# CSR8635-V1.net
KiCad netlist of a schematic drawn in EAGLE
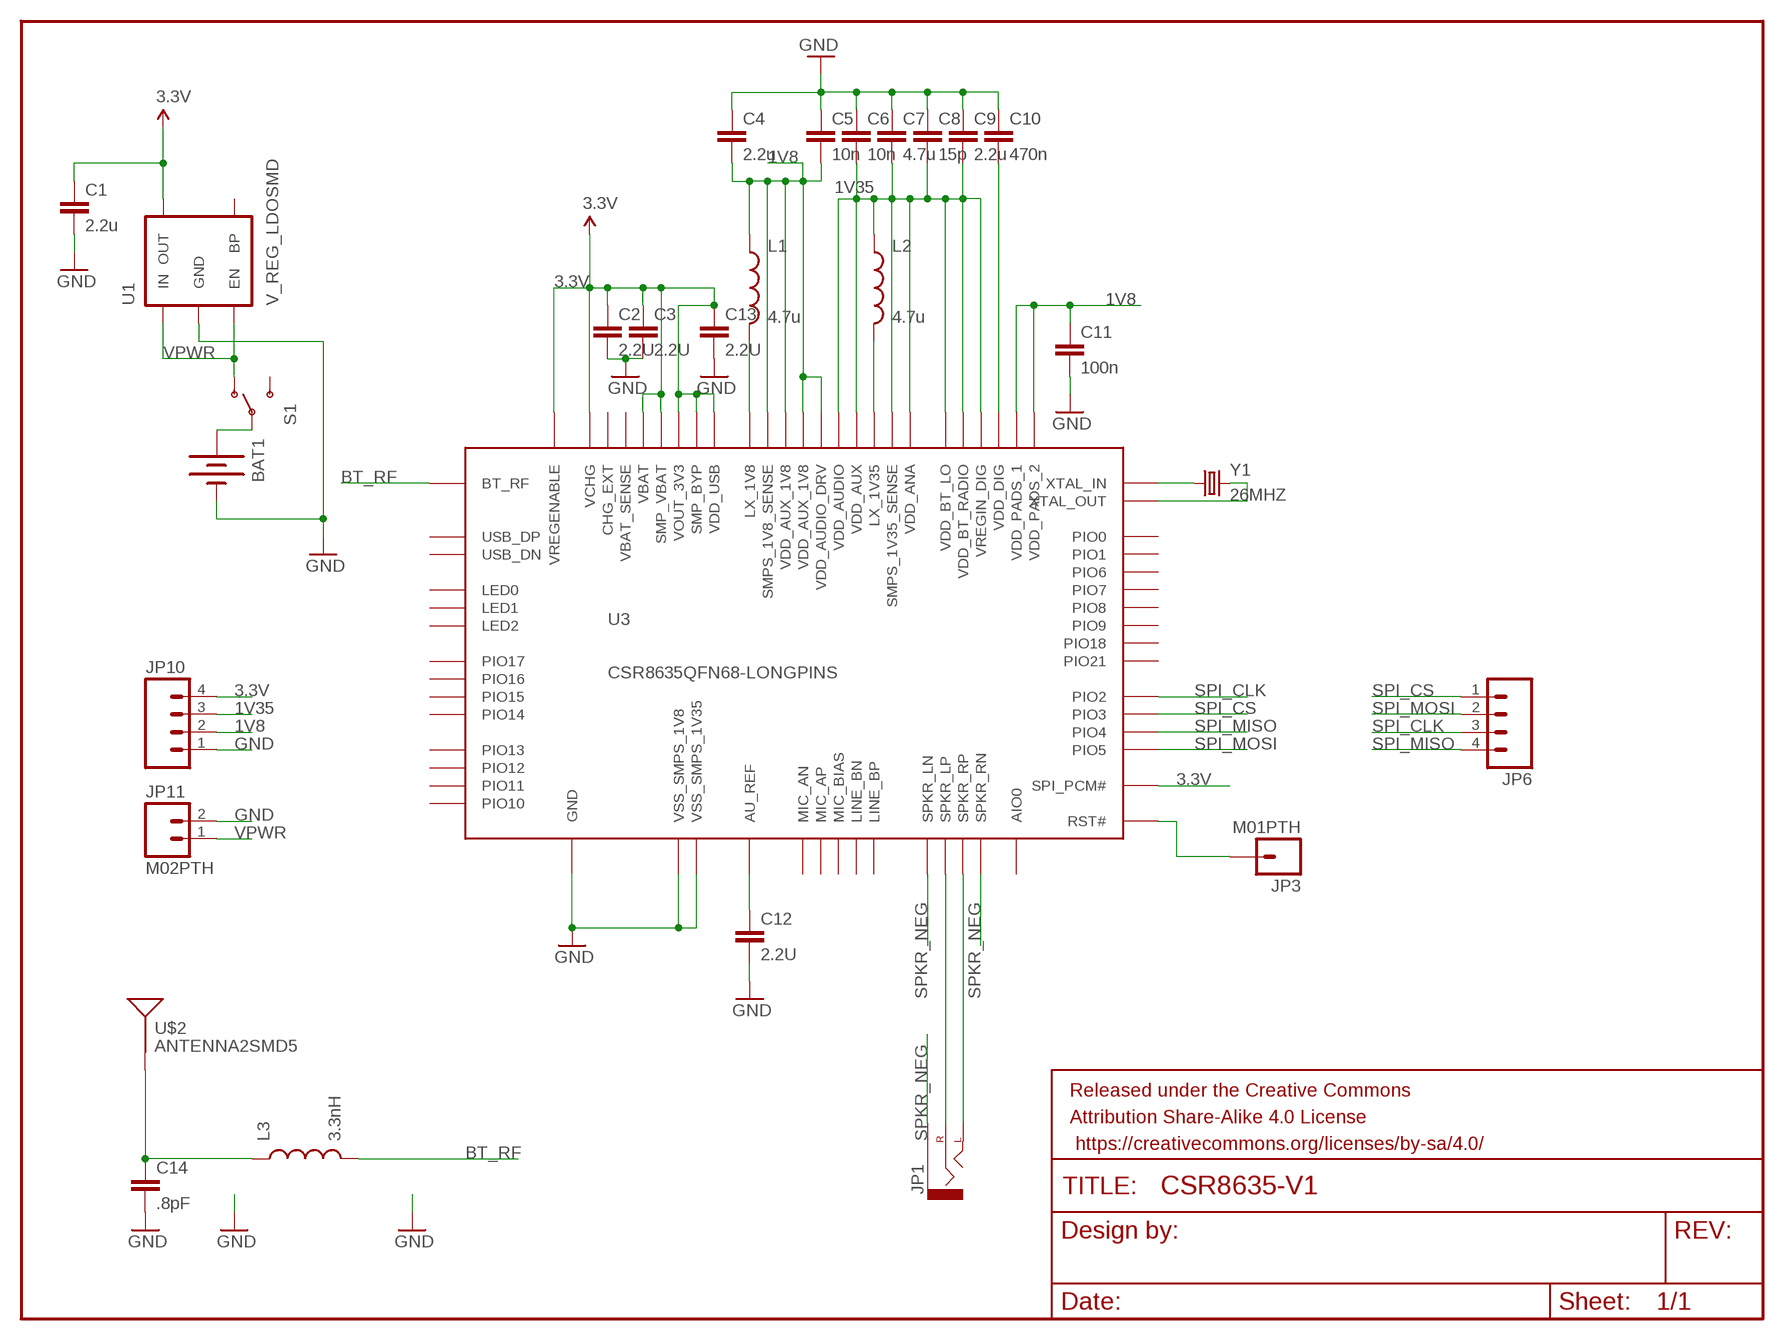
[diagram p0: schematic, sheet 1]

(export (version "E")
  (design (tool "Eeschema 10.0.6"))
  (components
    (comp (ref "BAT1")
      (value "BATTERY9V")
      (footprint "eagle-import:BATTCON_9V")
      (libsource (lib "eagle-import") (part "BATTERY9V"))
    )
    (comp (ref "C1")
      (value "2.2u")
      (footprint "eagle-import:0603-CAP")
      (libsource (lib "eagle-import") (part "CAP0603-CAP"))
    )
    (comp (ref "C2")
      (value "2.2U")
      (footprint "eagle-import:0603-CAP")
      (libsource (lib "eagle-import") (part "CAP0603-CAP"))
    )
    (comp (ref "C3")
      (value "2.2U")
      (footprint "eagle-import:0603-CAP")
      (libsource (lib "eagle-import") (part "CAP0603-CAP"))
    )
    (comp (ref "C4")
      (value "2.2u")
      (footprint "eagle-import:0603-CAP")
      (libsource (lib "eagle-import") (part "CAP0603-CAP"))
    )
    (comp (ref "C5")
      (value "10n")
      (footprint "eagle-import:0603-CAP")
      (libsource (lib "eagle-import") (part "CAP0603-CAP"))
    )
    (comp (ref "C6")
      (value "10n")
      (footprint "eagle-import:0603-CAP")
      (libsource (lib "eagle-import") (part "CAP0603-CAP"))
    )
    (comp (ref "C7")
      (value "4.7u")
      (footprint "eagle-import:0603-CAP")
      (libsource (lib "eagle-import") (part "CAP0603-CAP"))
    )
    (comp (ref "C8")
      (value "15p")
      (footprint "eagle-import:0603-CAP")
      (libsource (lib "eagle-import") (part "CAP0603-CAP"))
    )
    (comp (ref "C9")
      (value "2.2u")
      (footprint "eagle-import:0603-CAP")
      (libsource (lib "eagle-import") (part "CAP0603-CAP"))
    )
    (comp (ref "C10")
      (value "470n")
      (footprint "eagle-import:0603-CAP")
      (libsource (lib "eagle-import") (part "CAP0603-CAP"))
    )
    (comp (ref "C11")
      (value "100n")
      (footprint "eagle-import:0603-CAP")
      (libsource (lib "eagle-import") (part "CAP0603-CAP"))
    )
    (comp (ref "C12")
      (value "2.2U")
      (footprint "eagle-import:0603-CAP")
      (libsource (lib "eagle-import") (part "CAP0603-CAP"))
    )
    (comp (ref "C13")
      (value "2.2U")
      (footprint "eagle-import:0603-CAP")
      (libsource (lib "eagle-import") (part "CAP0603-CAP"))
    )
    (comp (ref "C14")
      (value ".8pF")
      (footprint "eagle-import:0603-CAP")
      (libsource (lib "eagle-import") (part "CAP0603-CAP"))
    )
    (comp (ref "FRAME1")
      (value "FRAME-LETTER")
      (footprint "eagle-import:CREATIVE_COMMONS")
      (libsource (lib "eagle-import") (part "FRAME-LETTER"))
    )
    (comp (ref "JP1")
      (value "AUDIO-JACKSMD2")
      (footprint "eagle-import:AUDIO-JACK-3.5MM-SMD")
      (libsource (lib "eagle-import") (part "AUDIO-JACKSMD2"))
    )
    (comp (ref "JP3")
      (value "M01PTH")
      (footprint "eagle-import:1X01")
      (libsource (lib "eagle-import") (part "M01PTH"))
    )
    (comp (ref "JP6")
      (value "M04PTH")
      (footprint "eagle-import:1X04")
      (libsource (lib "eagle-import") (part "M04PTH"))
    )
    (comp (ref "JP10")
      (value "M04PTH")
      (footprint "eagle-import:1X04")
      (libsource (lib "eagle-import") (part "M04PTH"))
    )
    (comp (ref "JP11")
      (value "M02PTH")
      (footprint "eagle-import:1X02")
      (libsource (lib "eagle-import") (part "M02PTH"))
    )
    (comp (ref "L1")
      (value "4.7u")
      (footprint "eagle-import:0805")
      (libsource (lib "eagle-import") (part "INDUCTOR0805"))
    )
    (comp (ref "L2")
      (value "4.7u")
      (footprint "eagle-import:0805")
      (libsource (lib "eagle-import") (part "INDUCTOR0805"))
    )
    (comp (ref "L3")
      (value "3.3nH")
      (footprint "eagle-import:0805")
      (libsource (lib "eagle-import") (part "INDUCTOR0805"))
    )
    (comp (ref "S1")
      (value "SWITCH-SPDTPTH")
      (footprint "eagle-import:SWITCH-SPDT")
      (libsource (lib "eagle-import") (part "SWITCH-SPDTPTH"))
    )
    (comp (ref "U$2")
      (value "ANTENNA2SMD5")
      (footprint "eagle-import:ANTENNA-CHIP5")
      (libsource (lib "eagle-import") (part "ANTENNA2SMD5"))
    )
    (comp (ref "U1")
      (value "V_REG_LDOSMD")
      (footprint "eagle-import:SOT23-5")
      (libsource (lib "eagle-import") (part "V_REG_LDOSMD"))
    )
    (comp (ref "U3")
      (value "CSR8635QFN68-LONGPINS")
      (footprint "eagle-import:QFN68")
      (libsource (lib "eagle-import") (part "CSR8635QFN68-LONGPINS"))
    )
    (comp (ref "Y1")
      (value "26MHZ")
      (footprint "eagle-import:HC49US")
      (libsource (lib "eagle-import") (part "CRYSTALHC49US"))
    )
  )
  (nets
    (net (code "1") (name "/1V8") (class "Default")
      (node (ref "C11") (pin "1") (pinfunction "1_1") (pintype "passive"))
      (node (ref "C4") (pin "2") (pinfunction "2_2") (pintype "passive"))
      (node (ref "C5") (pin "2") (pinfunction "2_2") (pintype "passive"))
      (node (ref "JP10") (pin "2") (pinfunction "2_2") (pintype "passive"))
      (node (ref "L1") (pin "1") (pinfunction "1_1") (pintype "passive"))
      (node (ref "U3") (pin "15") (pinfunction "VDD_AUX_1V8_15") (pintype "power_in"))
      (node (ref "U3") (pin "16") (pinfunction "VDD_AUX_1V8_16") (pintype "power_in"))
      (node (ref "U3") (pin "33") (pinfunction "VDD_PADS_1_33") (pintype "bidirectional"))
      (node (ref "U3") (pin "53") (pinfunction "SMPS_1V8_SENSE_53") (pintype "bidirectional"))
      (node (ref "U3") (pin "63") (pinfunction "VDD_PADS_2_63") (pintype "power_in"))
      (node (ref "U3") (pin "8") (pinfunction "VDD_AUDIO_DRV_8") (pintype "power_in"))
    )
    (net (code "2") (name "/1V35") (class "Default")
      (node (ref "C6") (pin "2") (pinfunction "2_2") (pintype "passive"))
      (node (ref "C7") (pin "2") (pinfunction "2_2") (pintype "passive"))
      (node (ref "C8") (pin "2") (pinfunction "2_2") (pintype "passive"))
      (node (ref "C9") (pin "2") (pinfunction "2_2") (pintype "passive"))
      (node (ref "JP10") (pin "3") (pinfunction "3_3") (pintype "passive"))
      (node (ref "L2") (pin "1") (pinfunction "1_1") (pintype "passive"))
      (node (ref "U3") (pin "11") (pinfunction "VDD_BT_RADIO_11") (pintype "power_in"))
      (node (ref "U3") (pin "13") (pinfunction "VDD_BT_LO_13") (pintype "power_in"))
      (node (ref "U3") (pin "14") (pinfunction "VDD_AUX_14") (pintype "power_in"))
      (node (ref "U3") (pin "17") (pinfunction "VDD_ANA_17") (pintype "power_in"))
      (node (ref "U3") (pin "3") (pinfunction "VDD_AUDIO_3") (pintype "power_in"))
      (node (ref "U3") (pin "39") (pinfunction "VREGIN_DIG_39") (pintype "bidirectional"))
      (node (ref "U3") (pin "52") (pinfunction "SMPS_1V35_SENSE_52") (pintype "bidirectional"))
    )
    (net (code "3") (name "/BT_RF") (class "Default")
      (node (ref "L3") (pin "2") (pinfunction "2_2") (pintype "passive"))
      (node (ref "U3") (pin "12") (pinfunction "BT_RF_12") (pintype "bidirectional"))
    )
    (net (code "4") (name "/SPI_CLK") (class "Default")
      (node (ref "JP6") (pin "3") (pinfunction "3_3") (pintype "passive"))
      (node (ref "U3") (pin "30") (pinfunction "PIO2_30") (pintype "bidirectional"))
    )
    (net (code "5") (name "/SPI_CS") (class "Default")
      (node (ref "JP6") (pin "1") (pinfunction "1_1") (pintype "passive"))
      (node (ref "U3") (pin "28") (pinfunction "PIO3_28") (pintype "bidirectional"))
    )
    (net (code "6") (name "/SPI_MISO") (class "Default")
      (node (ref "JP6") (pin "4") (pinfunction "4_4") (pintype "passive"))
      (node (ref "U3") (pin "24") (pinfunction "PIO4_24") (pintype "bidirectional"))
    )
    (net (code "7") (name "/SPI_MOSI") (class "Default")
      (node (ref "JP6") (pin "2") (pinfunction "2_2") (pintype "passive"))
      (node (ref "U3") (pin "34") (pinfunction "PIO5_34") (pintype "bidirectional"))
    )
    (net (code "8") (name "/SPKR_NEG") (class "Default")
      (node (ref "JP1") (pin "SLEEVE") (pinfunction "SLEEVE_SLEEVE") (pintype "bidirectional"))
      (node (ref "U3") (pin "6") (pinfunction "SPKR_RN_6") (pintype "bidirectional"))
      (node (ref "U3") (pin "9") (pinfunction "SPKR_LN_9") (pintype "bidirectional"))
    )
    (net (code "9") (name "/VPWR") (class "Default")
      (node (ref "JP11") (pin "1") (pinfunction "1_1") (pintype "passive"))
      (node (ref "S1") (pin "1") (pinfunction "O_1") (pintype "passive"))
      (node (ref "U1") (pin "1") (pinfunction "IN_1") (pintype "input"))
      (node (ref "U1") (pin "3") (pinfunction "EN_3") (pintype "input"))
    )
    (net (code "10") (name "3.3V") (class "Default")
      (node (ref "C1") (pin "1") (pinfunction "1_1") (pintype "passive"))
      (node (ref "C13") (pin "1") (pinfunction "1_1") (pintype "passive"))
      (node (ref "C2") (pin "1") (pinfunction "1_1") (pintype "passive"))
      (node (ref "C3") (pin "1") (pinfunction "1_1") (pintype "passive"))
      (node (ref "JP10") (pin "4") (pinfunction "4_4") (pintype "passive"))
      (node (ref "U1") (pin "5") (pinfunction "OUT_5") (pintype "passive"))
      (node (ref "U3") (pin "29") (pinfunction "SPI_PCM#_29") (pintype "bidirectional"))
      (node (ref "U3") (pin "40") (pinfunction "VREGENABLE_40") (pintype "bidirectional"))
      (node (ref "U3") (pin "41") (pinfunction "VOUT_3V3_41") (pintype "power_in"))
      (node (ref "U3") (pin "42") (pinfunction "VCHG_42") (pintype "bidirectional"))
      (node (ref "U3") (pin "45") (pinfunction "VBAT_45") (pintype "power_in"))
      (node (ref "U3") (pin "48") (pinfunction "SMP_VBAT_48") (pintype "bidirectional"))
      (node (ref "U3") (pin "49") (pinfunction "SMP_BYP_49") (pintype "bidirectional"))
      (node (ref "U3") (pin "54") (pinfunction "VDD_USB_54") (pintype "power_in"))
    )
    (net (code "11") (name "GND") (class "Default")
      (node (ref "BAT1") (pin "-") (pinfunction "-_-") (pintype "power_in"))
      (node (ref "C1") (pin "2") (pinfunction "2_2") (pintype "passive"))
      (node (ref "C10") (pin "1") (pinfunction "1_1") (pintype "passive"))
      (node (ref "C11") (pin "2") (pinfunction "2_2") (pintype "passive"))
      (node (ref "C12") (pin "2") (pinfunction "2_2") (pintype "passive"))
      (node (ref "C13") (pin "2") (pinfunction "2_2") (pintype "passive"))
      (node (ref "C14") (pin "2") (pinfunction "2_2") (pintype "passive"))
      (node (ref "C2") (pin "2") (pinfunction "2_2") (pintype "passive"))
      (node (ref "C3") (pin "2") (pinfunction "2_2") (pintype "passive"))
      (node (ref "C4") (pin "1") (pinfunction "1_1") (pintype "passive"))
      (node (ref "C5") (pin "1") (pinfunction "1_1") (pintype "passive"))
      (node (ref "C6") (pin "1") (pinfunction "1_1") (pintype "passive"))
      (node (ref "C7") (pin "1") (pinfunction "1_1") (pintype "passive"))
      (node (ref "C8") (pin "1") (pinfunction "1_1") (pintype "passive"))
      (node (ref "C9") (pin "1") (pinfunction "1_1") (pintype "passive"))
      (node (ref "JP10") (pin "1") (pinfunction "1_1") (pintype "passive"))
      (node (ref "JP11") (pin "2") (pinfunction "2_2") (pintype "passive"))
      (node (ref "U1") (pin "2") (pinfunction "GND_2") (pintype "input"))
      (node (ref "U3") (pin "46") (pinfunction "VSS_SMPS_1V8_46") (pintype "bidirectional"))
      (node (ref "U3") (pin "51") (pinfunction "VSS_SMPS_1V35_51") (pintype "bidirectional"))
      (node (ref "U3") (pin "CNTR") (pinfunction "GND_CNTR") (pintype "bidirectional"))
      (node (ref "U3") (pin "CNTR1") (pinfunction "GND_CNTR1") (pintype "bidirectional"))
      (node (ref "U3") (pin "CNTR2") (pinfunction "GND_CNTR2") (pintype "bidirectional"))
      (node (ref "U3") (pin "CNTR3") (pinfunction "GND_CNTR3") (pintype "bidirectional"))
    )
    (net (code "12") (name "Net-(JP1-LEFT)") (class "Default")
      (node (ref "JP1") (pin "TIP") (pinfunction "LEFT_TIP") (pintype "bidirectional"))
      (node (ref "U3") (pin "7") (pinfunction "SPKR_RP_7") (pintype "bidirectional"))
    )
    (net (code "13") (name "Net-(JP1-RIGHT)") (class "Default")
      (node (ref "JP1") (pin "RING") (pinfunction "RIGHT_RING") (pintype "bidirectional"))
      (node (ref "U3") (pin "10") (pinfunction "SPKR_LP_10") (pintype "bidirectional"))
    )
    (net (code "14") (name "Net-(S1-P)") (class "Default")
      (node (ref "BAT1") (pin "+") (pinfunction "+_+") (pintype "power_in"))
      (node (ref "S1") (pin "2") (pinfunction "P_2") (pintype "passive"))
    )
    (net (code "15") (name "Net-(U$2-SIGNAL)") (class "Default")
      (node (ref "C14") (pin "1") (pinfunction "1_1") (pintype "passive"))
      (node (ref "L3") (pin "1") (pinfunction "1_1") (pintype "passive"))
      (node (ref "U$2") (pin "FEED") (pinfunction "SIGNAL_FEED") (pintype "bidirectional"))
    )
    (net (code "16") (name "Net-(U3-AU_REF)") (class "Default")
      (node (ref "C12") (pin "1") (pinfunction "1_1") (pintype "passive"))
      (node (ref "U3") (pin "1") (pinfunction "AU_REF_1") (pintype "bidirectional"))
    )
    (net (code "17") (name "Net-(U3-LX_1V8)") (class "Default")
      (node (ref "L1") (pin "2") (pinfunction "2_2") (pintype "passive"))
      (node (ref "U3") (pin "47") (pinfunction "LX_1V8_47") (pintype "bidirectional"))
    )
    (net (code "18") (name "Net-(U3-LX_1V35)") (class "Default")
      (node (ref "L2") (pin "2") (pinfunction "2_2") (pintype "passive"))
      (node (ref "U3") (pin "50") (pinfunction "LX_1V35_50") (pintype "bidirectional"))
    )
    (net (code "19") (name "Net-(U3-RST#)") (class "Default")
      (node (ref "JP3") (pin "1") (pinfunction "1_1") (pintype "passive"))
      (node (ref "U3") (pin "35") (pinfunction "RST#_35") (pintype "bidirectional"))
    )
    (net (code "20") (name "Net-(U3-VDD_DIG)") (class "Default")
      (node (ref "C10") (pin "2") (pinfunction "2_2") (pintype "passive"))
      (node (ref "U3") (pin "38") (pinfunction "VDD_DIG_38") (pintype "power_in"))
    )
    (net (code "21") (name "Net-(U3-XTAL_IN)") (class "Default")
      (node (ref "U3") (pin "19") (pinfunction "XTAL_IN_19") (pintype "bidirectional"))
      (node (ref "Y1") (pin "1") (pinfunction "1_1") (pintype "passive"))
    )
    (net (code "22") (name "Net-(U3-XTAL_OUT)") (class "Default")
      (node (ref "U3") (pin "18") (pinfunction "XTAL_OUT_18") (pintype "bidirectional"))
      (node (ref "Y1") (pin "2") (pinfunction "2_2") (pintype "passive"))
    )
    (net (code "23") (name "unconnected-(S1-S-Pad3)") (class "Default")
      (node (ref "S1") (pin "3") (pinfunction "S_3") (pintype "passive"))
    )
    (net (code "24") (name "unconnected-(U1-BP-Pad4)") (class "Default")
      (node (ref "U1") (pin "4") (pinfunction "BP_4") (pintype "input"))
    )
    (net (code "25") (name "unconnected-(U3-AIO0-Pad20)") (class "Default")
      (node (ref "U3") (pin "20") (pinfunction "AIO0_20") (pintype "bidirectional"))
    )
    (net (code "26") (name "unconnected-(U3-CHG_EXT-Pad43)") (class "Default")
      (node (ref "U3") (pin "43") (pinfunction "CHG_EXT_43") (pintype "bidirectional"))
    )
    (net (code "27") (name "unconnected-(U3-LED0-Pad37)") (class "Default")
      (node (ref "U3") (pin "37") (pinfunction "LED0_37") (pintype "bidirectional"))
    )
    (net (code "28") (name "unconnected-(U3-LED1-Pad36)") (class "Default")
      (node (ref "U3") (pin "36") (pinfunction "LED1_36") (pintype "bidirectional"))
    )
    (net (code "29") (name "unconnected-(U3-LED2-Pad66)") (class "Default")
      (node (ref "U3") (pin "66") (pinfunction "LED2_66") (pintype "bidirectional"))
    )
    (net (code "30") (name "unconnected-(U3-LINE_BN-Pad4)") (class "Default")
      (node (ref "U3") (pin "4") (pinfunction "LINE_BN_4") (pintype "bidirectional"))
    )
    (net (code "31") (name "unconnected-(U3-LINE_BP-Pad5)") (class "Default")
      (node (ref "U3") (pin "5") (pinfunction "LINE_BP_5") (pintype "bidirectional"))
    )
    (net (code "32") (name "unconnected-(U3-MIC_AN-Pad67)") (class "Default")
      (node (ref "U3") (pin "67") (pinfunction "MIC_AN_67") (pintype "bidirectional"))
    )
    (net (code "33") (name "unconnected-(U3-MIC_AP-Pad68)") (class "Default")
      (node (ref "U3") (pin "68") (pinfunction "MIC_AP_68") (pintype "bidirectional"))
    )
    (net (code "34") (name "unconnected-(U3-MIC_BIAS-Pad2)") (class "Default")
      (node (ref "U3") (pin "2") (pinfunction "MIC_BIAS_2") (pintype "bidirectional"))
    )
    (net (code "35") (name "unconnected-(U3-PIO0-Pad59)") (class "Default")
      (node (ref "U3") (pin "59") (pinfunction "PIO0_59") (pintype "bidirectional"))
    )
    (net (code "36") (name "unconnected-(U3-PIO1-Pad60)") (class "Default")
      (node (ref "U3") (pin "60") (pinfunction "PIO1_60") (pintype "bidirectional"))
    )
    (net (code "37") (name "unconnected-(U3-PIO6-Pad62)") (class "Default")
      (node (ref "U3") (pin "62") (pinfunction "PIO6_62") (pintype "bidirectional"))
    )
    (net (code "38") (name "unconnected-(U3-PIO7-Pad57)") (class "Default")
      (node (ref "U3") (pin "57") (pinfunction "PIO7_57") (pintype "bidirectional"))
    )
    (net (code "39") (name "unconnected-(U3-PIO8-Pad61)") (class "Default")
      (node (ref "U3") (pin "61") (pinfunction "PIO8_61") (pintype "bidirectional"))
    )
    (net (code "40") (name "unconnected-(U3-PIO9-Pad58)") (class "Default")
      (node (ref "U3") (pin "58") (pinfunction "PIO9_58") (pintype "bidirectional"))
    )
    (net (code "41") (name "unconnected-(U3-PIO10-Pad25)") (class "Default")
      (node (ref "U3") (pin "25") (pinfunction "PIO10_25") (pintype "bidirectional"))
    )
    (net (code "42") (name "unconnected-(U3-PIO11-Pad26)") (class "Default")
      (node (ref "U3") (pin "26") (pinfunction "PIO11_26") (pintype "bidirectional"))
    )
    (net (code "43") (name "unconnected-(U3-PIO12-Pad22)") (class "Default")
      (node (ref "U3") (pin "22") (pinfunction "PIO12_22") (pintype "bidirectional"))
    )
    (net (code "44") (name "unconnected-(U3-PIO13-Pad31)") (class "Default")
      (node (ref "U3") (pin "31") (pinfunction "PIO13_31") (pintype "bidirectional"))
    )
    (net (code "45") (name "unconnected-(U3-PIO14-Pad23)") (class "Default")
      (node (ref "U3") (pin "23") (pinfunction "PIO14_23") (pintype "bidirectional"))
    )
    (net (code "46") (name "unconnected-(U3-PIO15-Pad21)") (class "Default")
      (node (ref "U3") (pin "21") (pinfunction "PIO15_21") (pintype "bidirectional"))
    )
    (net (code "47") (name "unconnected-(U3-PIO16-Pad27)") (class "Default")
      (node (ref "U3") (pin "27") (pinfunction "PIO16_27") (pintype "bidirectional"))
    )
    (net (code "48") (name "unconnected-(U3-PIO17-Pad32)") (class "Default")
      (node (ref "U3") (pin "32") (pinfunction "PIO17_32") (pintype "bidirectional"))
    )
    (net (code "49") (name "unconnected-(U3-PIO18-Pad65)") (class "Default")
      (node (ref "U3") (pin "65") (pinfunction "PIO18_65") (pintype "bidirectional"))
    )
    (net (code "50") (name "unconnected-(U3-PIO21-Pad64)") (class "Default")
      (node (ref "U3") (pin "64") (pinfunction "PIO21_64") (pintype "bidirectional"))
    )
    (net (code "51") (name "unconnected-(U3-USB_DN-Pad55)") (class "Default")
      (node (ref "U3") (pin "55") (pinfunction "USB_DN_55") (pintype "bidirectional"))
    )
    (net (code "52") (name "unconnected-(U3-USB_DP-Pad56)") (class "Default")
      (node (ref "U3") (pin "56") (pinfunction "USB_DP_56") (pintype "bidirectional"))
    )
    (net (code "53") (name "unconnected-(U3-VBAT_SENSE-Pad44)") (class "Default")
      (node (ref "U3") (pin "44") (pinfunction "VBAT_SENSE_44") (pintype "bidirectional"))
    )
  )
)
